# wifi-power.net
KiCad netlist of a schematic drawn in EasyEDA Pro
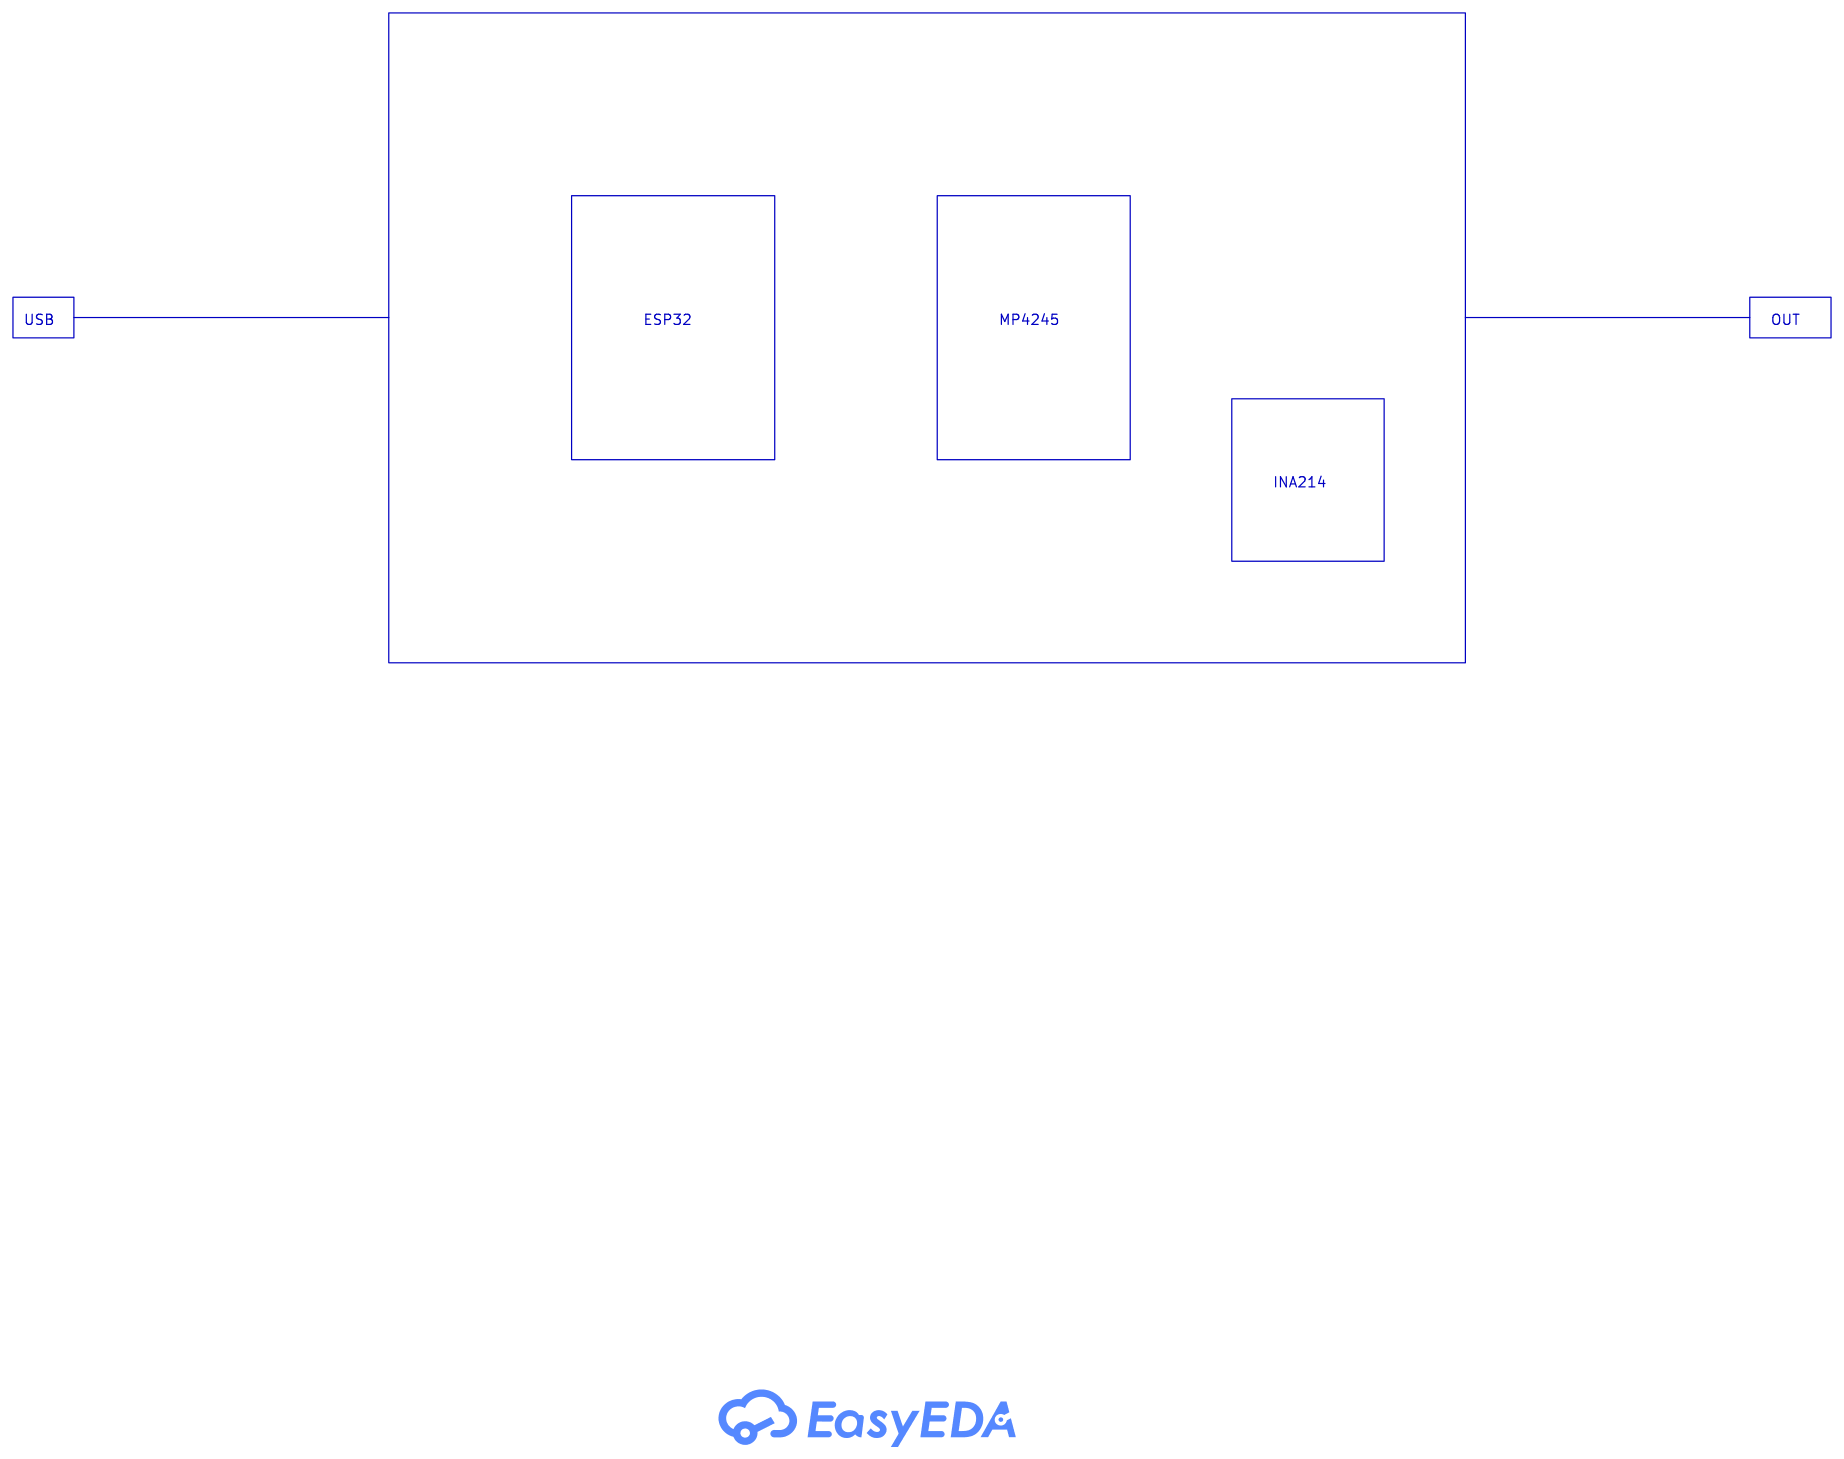
[diagram p0: P1]
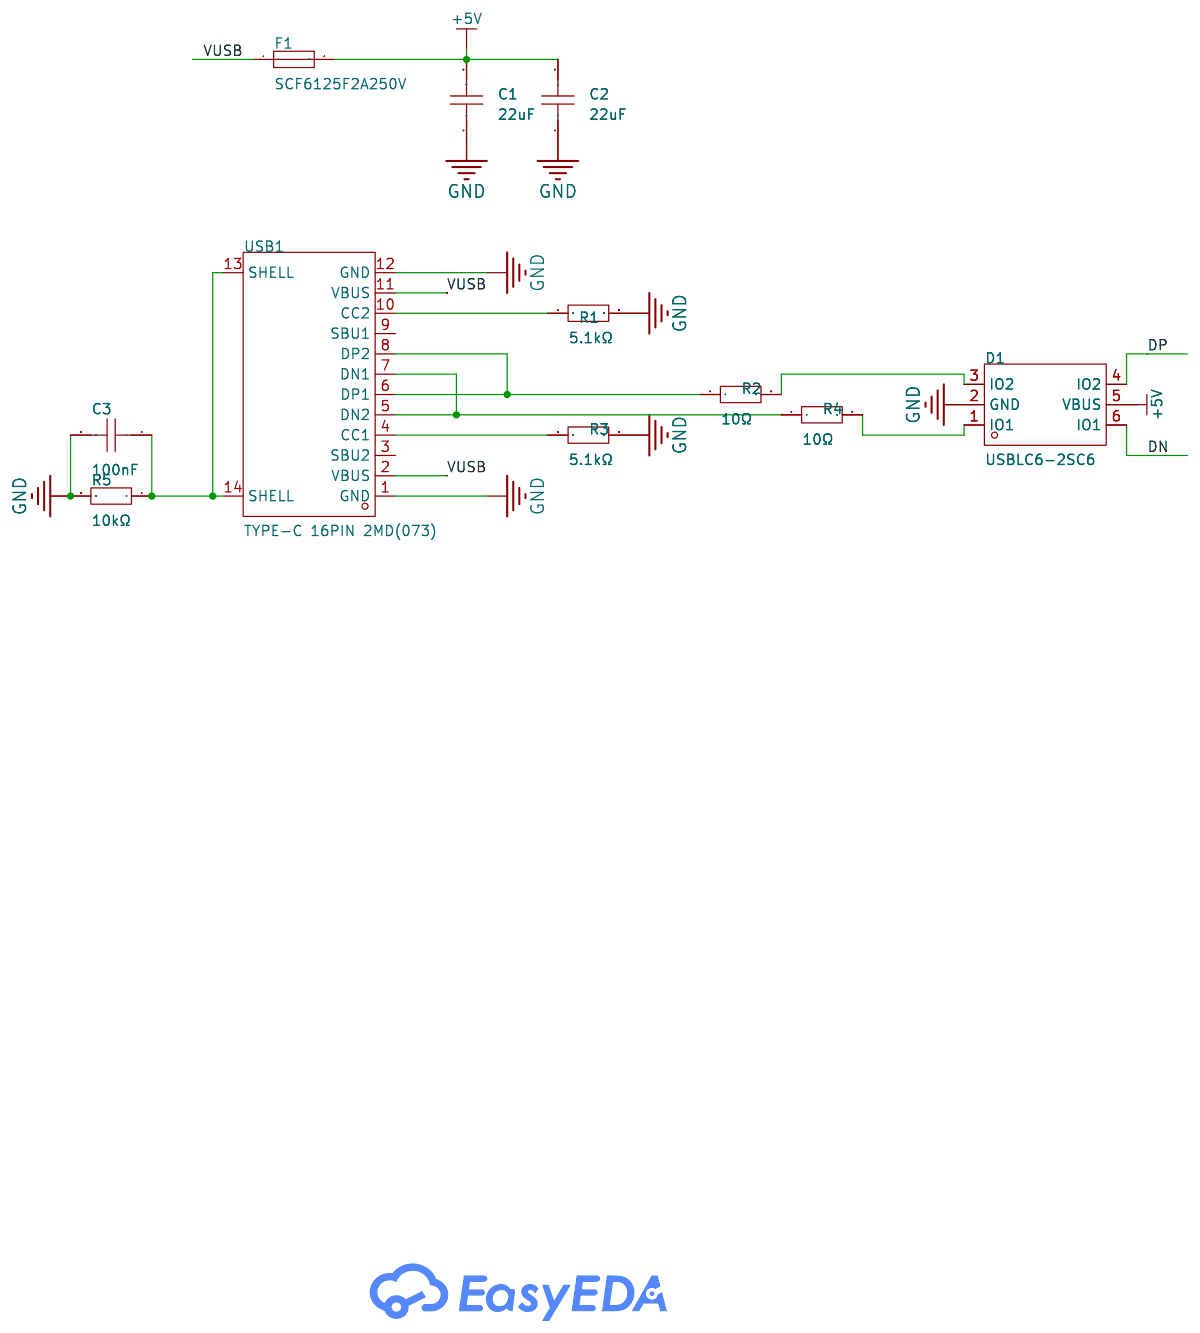
[diagram p1: USB]
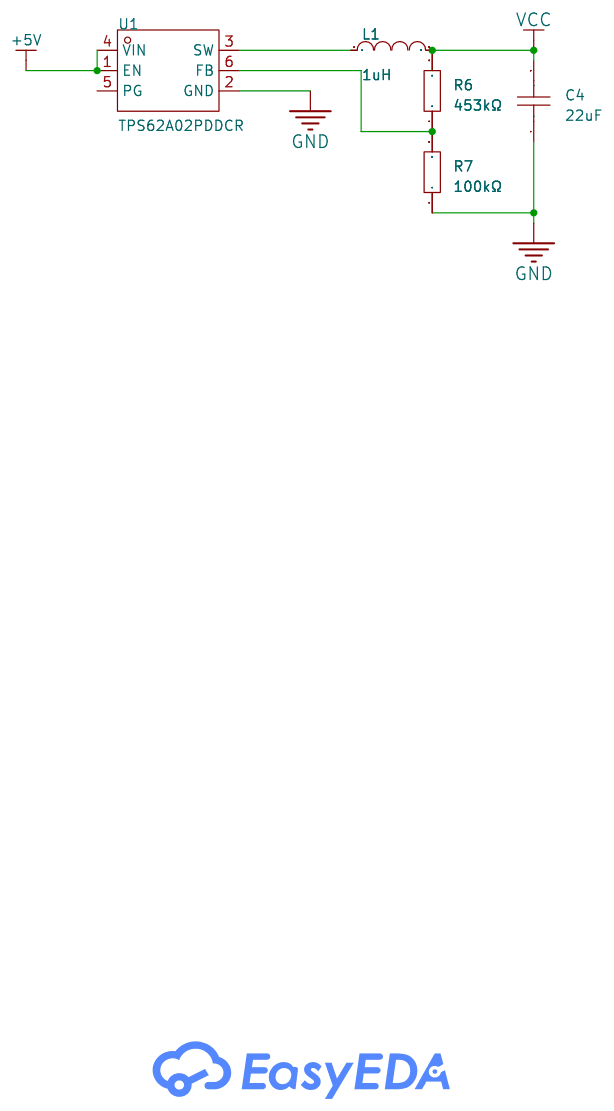
[diagram p2: REG]
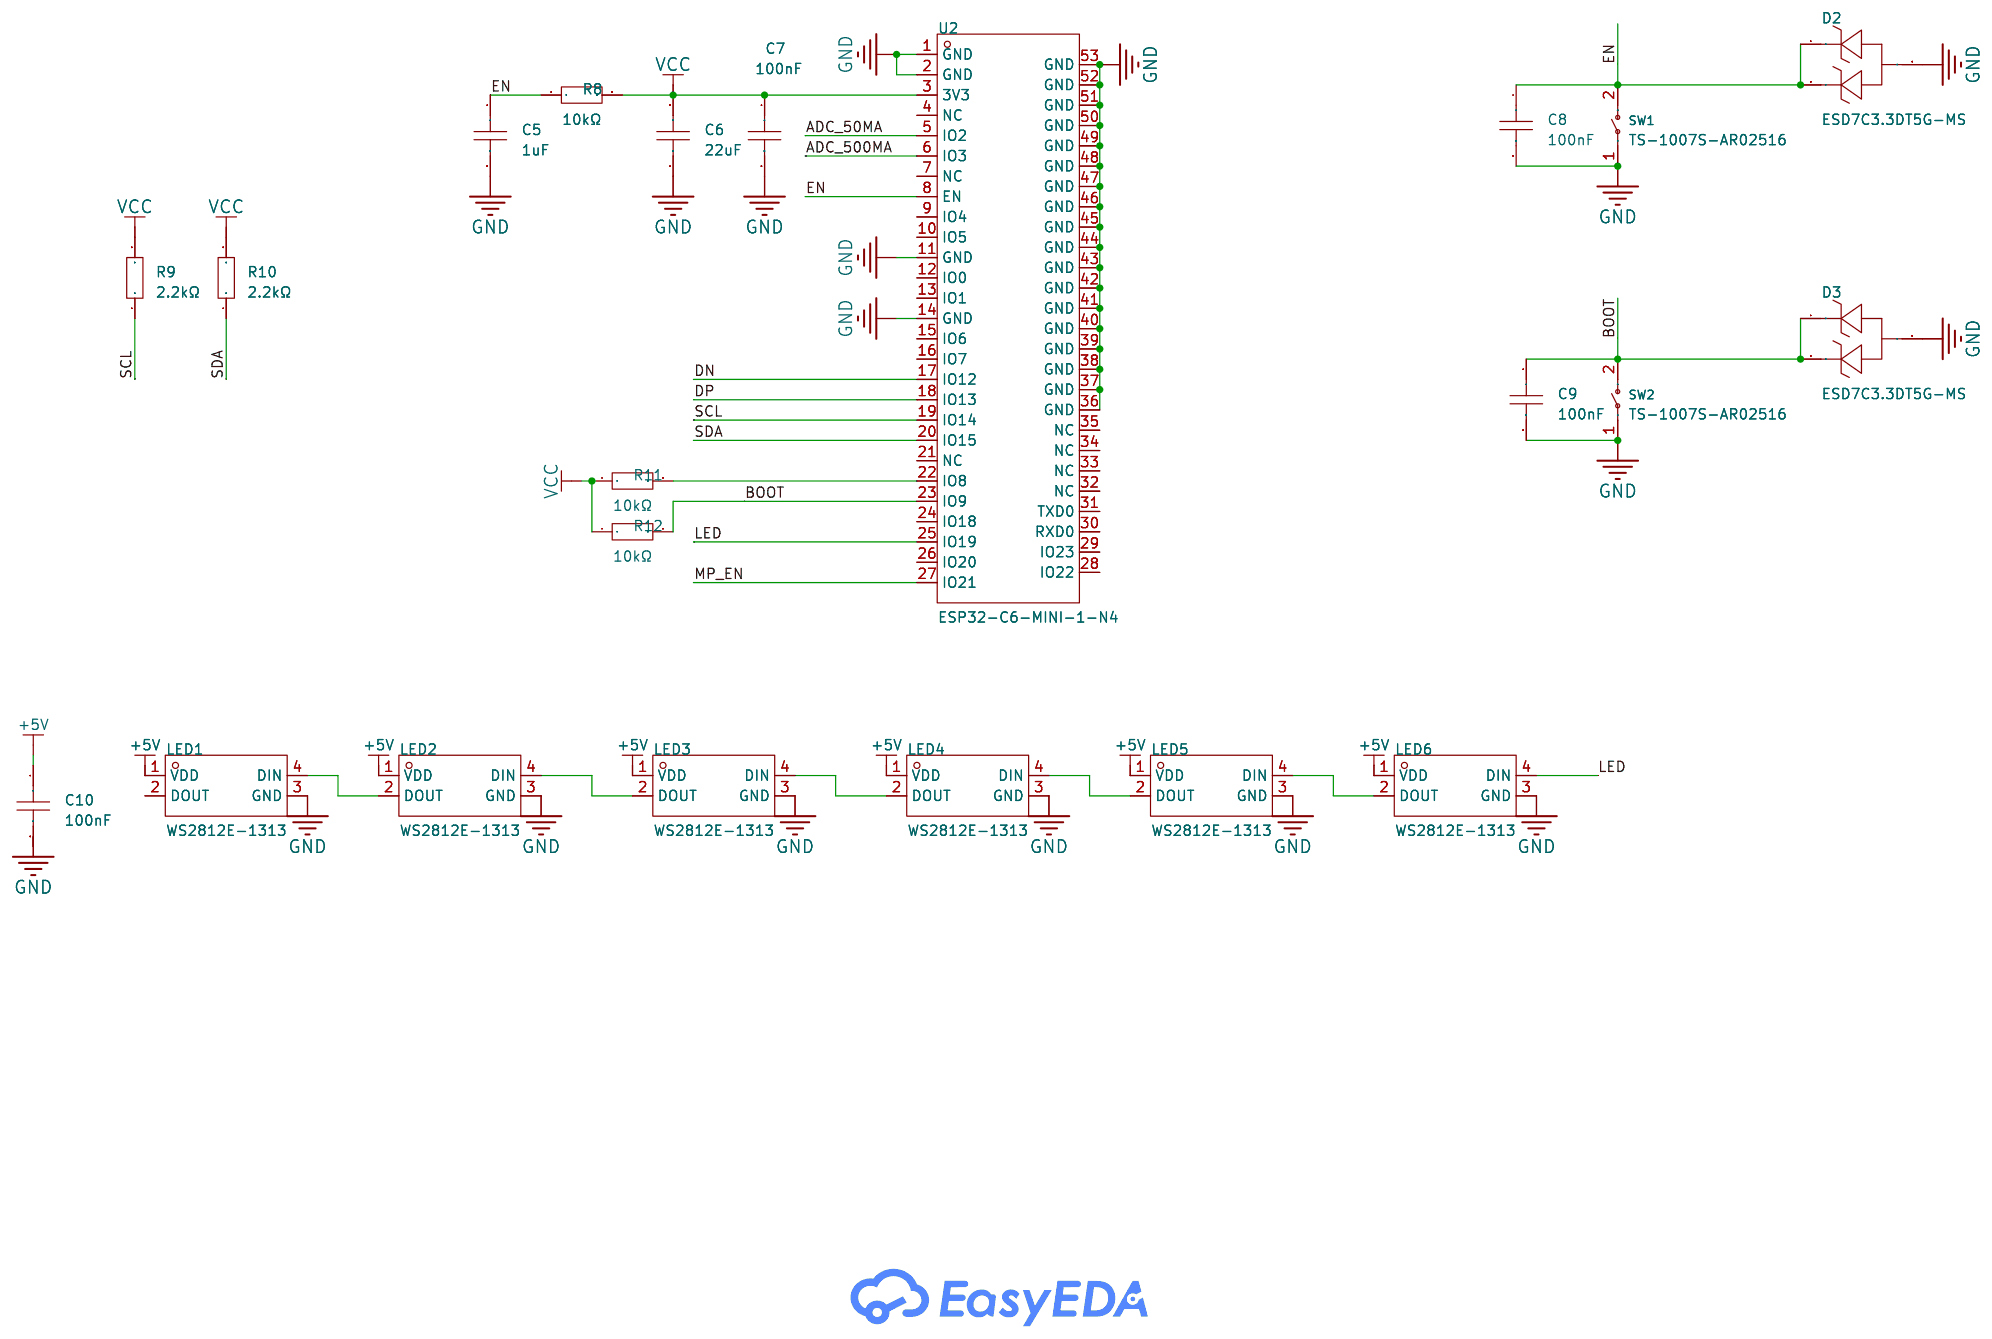
[diagram p3: ESP32]
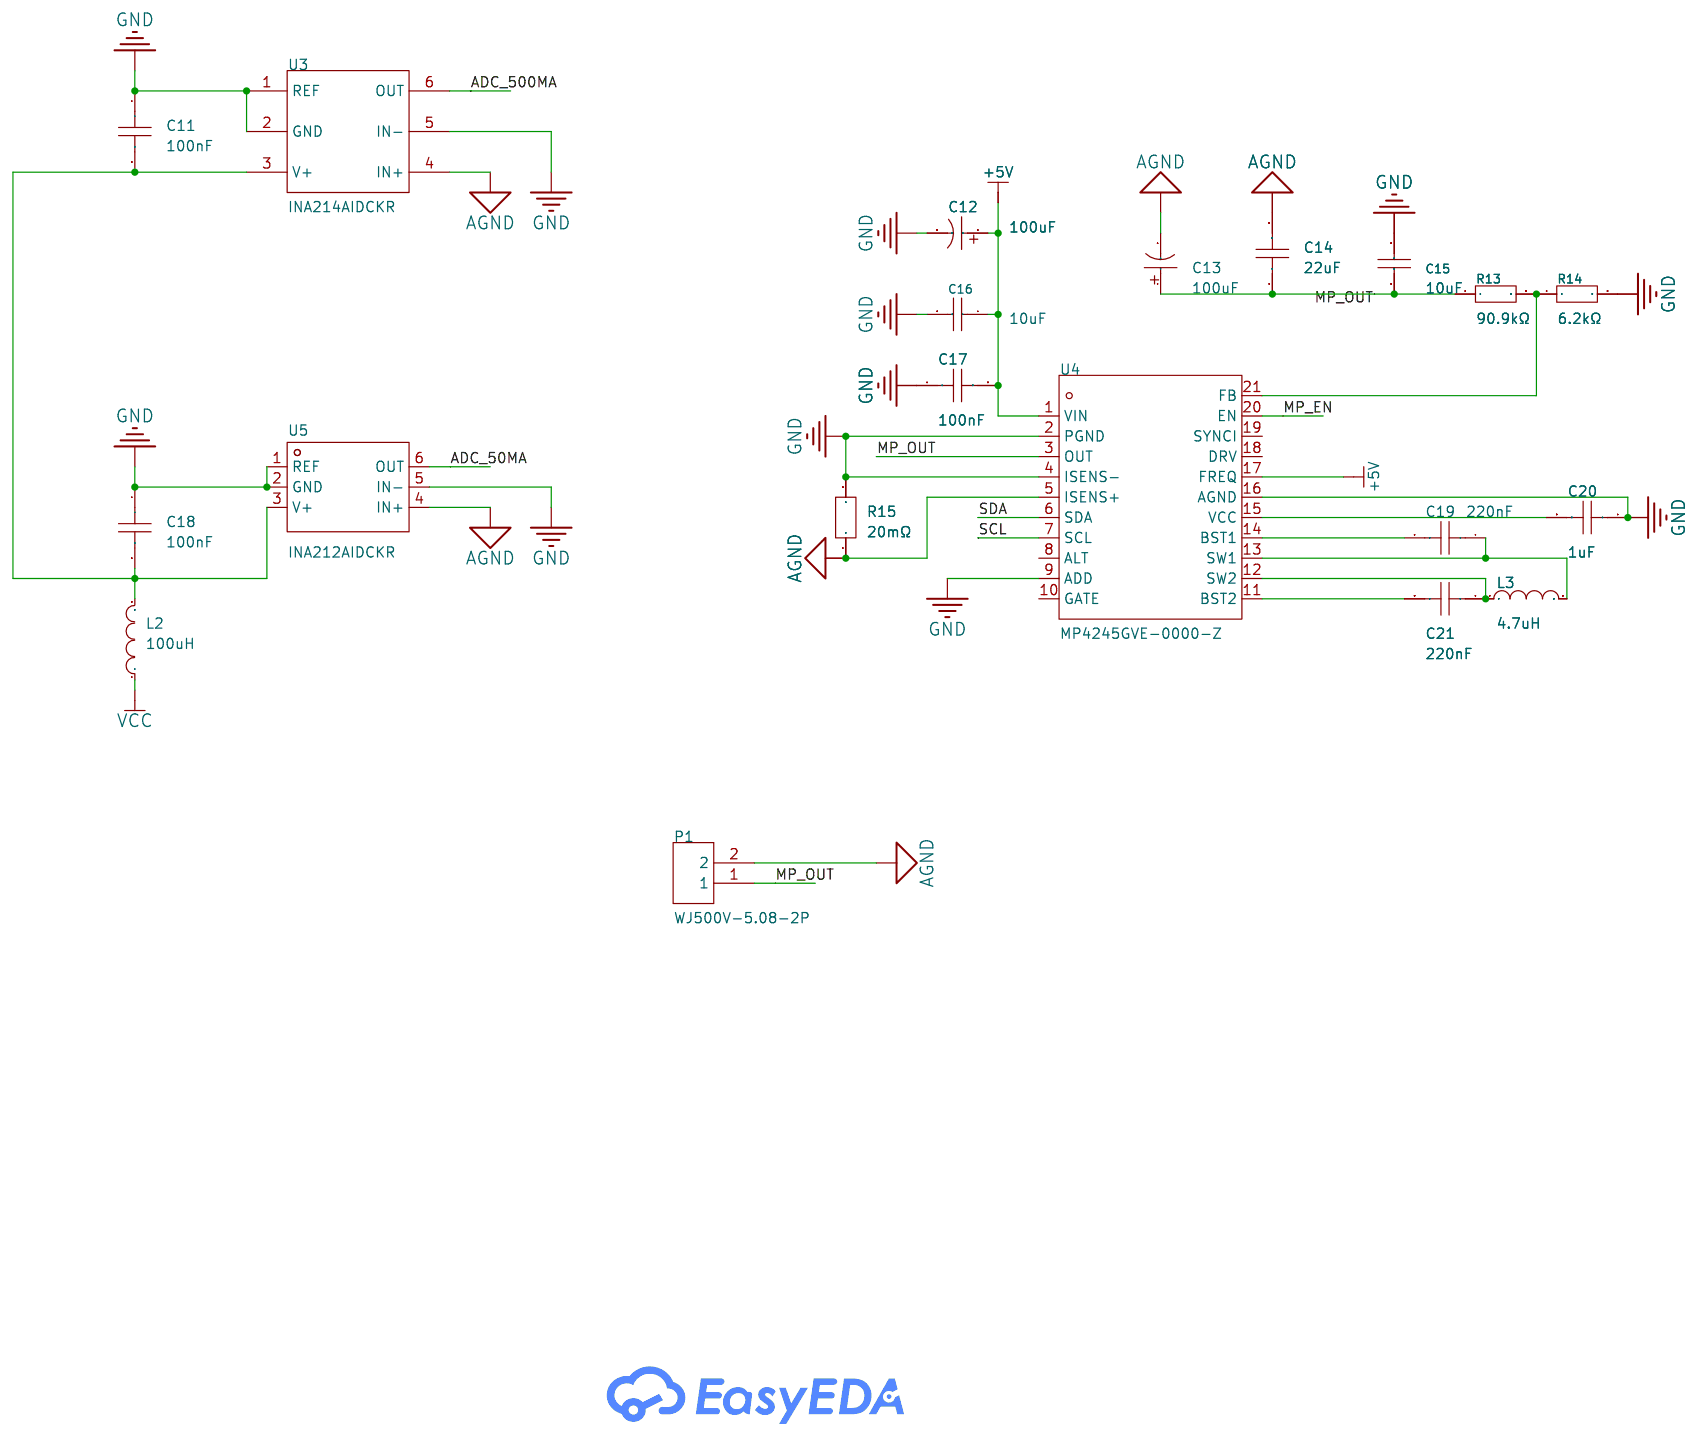
[diagram p4: MP4245]

(export (version "E")
  (design (tool "Eeschema 10.0.6"))
  (components
    (comp (ref "C1")
      (value "22uF")
      (footprint "easyedapro:C0805")
      (fields
        (field (name "Manufacturer Part") "CL21A226MAYNNNE")
        (field (name "Manufacturer") "SAMSUNG(三星)")
      )
      (libsource (lib "easyedapro") (part "CL21A226MAYNNNE"))
    )
    (comp (ref "C2")
      (value "22uF")
      (footprint "easyedapro:C0805")
      (fields
        (field (name "Manufacturer Part") "CL21A226MAYNNNE")
        (field (name "Manufacturer") "SAMSUNG(三星)")
      )
      (libsource (lib "easyedapro") (part "CL21A226MAYNNNE"))
    )
    (comp (ref "C3")
      (value "100nF")
      (footprint "easyedapro:C0603")
      (fields
        (field (name "Manufacturer Part") "CC0603KRX7R9BB104")
        (field (name "Manufacturer") "YAGEO(国巨)")
      )
      (libsource (lib "easyedapro") (part "CAP"))
    )
    (comp (ref "D1")
      (value "USBLC6-2SC6")
      (footprint "easyedapro:SOT-23-6_L2.9-W1.6-P0.95-LS2.8-BL")
      (fields (field (name "Manufacturer") "TECH PUBLIC(台舟)"))
      (libsource (lib "easyedapro") (part "USBLC6-2SC6_C2827654"))
    )
    (comp (ref "F1")
      (value "SCF6125F2A250V")
      (footprint "easyedapro:FUSE-SMD_L6.3-W2.7")
      (fields (field (name "Manufacturer") "SET(赛尔特)"))
      (libsource (lib "easyedapro") (part "SCF6125F2A250V"))
    )
    (comp (ref "R1")
      (value "5.1kΩ")
      (footprint "easyedapro:R0603")
      (fields (field (name "Manufacturer Part") "FRC0603J512 TS") (field (name "Manufacturer") "FOJAN(富捷)"))
      (libsource (lib "easyedapro") (part "Res"))
    )
    (comp (ref "R2")
      (value "10Ω")
      (footprint "easyedapro:R0603")
      (fields
        (field (name "Manufacturer Part") "0603WAF100JT5E")
        (field (name "Manufacturer") "UNI-ROYAL(厚声)")
      )
      (libsource (lib "easyedapro") (part "Res"))
    )
    (comp (ref "R3")
      (value "5.1kΩ")
      (footprint "easyedapro:R0603")
      (fields (field (name "Manufacturer Part") "FRC0603J512 TS") (field (name "Manufacturer") "FOJAN(富捷)"))
      (libsource (lib "easyedapro") (part "Res"))
    )
    (comp (ref "R4")
      (value "10Ω")
      (footprint "easyedapro:R0603")
      (fields
        (field (name "Manufacturer Part") "0603WAF100JT5E")
        (field (name "Manufacturer") "UNI-ROYAL(厚声)")
      )
      (libsource (lib "easyedapro") (part "Res"))
    )
    (comp (ref "R5")
      (value "10kΩ")
      (footprint "easyedapro:R0603")
      (fields (field (name "Manufacturer Part") "FRC0603J103TS") (field (name "Manufacturer") "FOJAN(富捷)"))
      (libsource (lib "easyedapro") (part "Res"))
    )
    (comp (ref "USB1")
      (value "TYPE-C 16PIN 2MD(073)")
      (footprint "easyedapro:USB-C-SMD_TYPE-C-6PIN-2MD-073")
      (fields (field (name "Manufacturer") "SHOU HAN(首韩)"))
      (libsource (lib "easyedapro") (part "TYPE-C 16PIN 2MD(073)"))
    )
    (comp (ref "C4")
      (value "22uF")
      (footprint "easyedapro:C0805")
      (fields
        (field (name "Manufacturer Part") "CL21A226MAYNNNE")
        (field (name "Manufacturer") "SAMSUNG(三星)")
      )
      (libsource (lib "easyedapro") (part "CL21A226MAYNNNE"))
    )
    (comp (ref "L1")
      (value "1uH")
      (footprint "easyedapro:L0806")
      (fields
        (field (name "Manufacturer Part") "DFE201610E-1R0M=P2")
        (field (name "Manufacturer") "muRata(村田)")
      )
      (libsource (lib "easyedapro") (part "DFE201610E-1R0M=P2"))
    )
    (comp (ref "R6")
      (value "453kΩ")
      (footprint "easyedapro:R0603")
      (fields
        (field (name "Manufacturer Part") "0603WAF4533T5E")
        (field (name "Manufacturer") "UNI-ROYAL(厚声)")
      )
      (libsource (lib "easyedapro") (part "Res"))
    )
    (comp (ref "R7")
      (value "100kΩ")
      (footprint "easyedapro:R0603")
      (fields (field (name "Manufacturer Part") "RC0603FR-07100KL") (field (name "Manufacturer") "YAGEO(国巨)"))
      (libsource (lib "easyedapro") (part "Res"))
    )
    (comp (ref "U1")
      (value "TPS62A02PDDCR")
      (footprint "easyedapro:SOT-23-6_L2.9-W1.6-P0.95-LS2.9-BL")
      (fields (field (name "Manufacturer") "TI(德州仪器)"))
      (libsource (lib "easyedapro") (part "TPS62A02PDDCR"))
    )
    (comp (ref "C5")
      (value "1uF")
      (footprint "easyedapro:C0603")
      (fields (field (name "Manufacturer Part") "0603F105Z100CT") (field (name "Manufacturer") "Walsin(华新科)"))
      (libsource (lib "easyedapro") (part "CAP"))
    )
    (comp (ref "C6")
      (value "22uF")
      (footprint "easyedapro:C0805")
      (fields
        (field (name "Manufacturer Part") "CL21A226MAYNNNE")
        (field (name "Manufacturer") "SAMSUNG(三星)")
      )
      (libsource (lib "easyedapro") (part "CL21A226MAYNNNE"))
    )
    (comp (ref "C7")
      (value "100nF")
      (footprint "easyedapro:C0603")
      (fields
        (field (name "Manufacturer Part") "CC0603KRX7R9BB104")
        (field (name "Manufacturer") "YAGEO(国巨)")
      )
      (libsource (lib "easyedapro") (part "CAP"))
    )
    (comp (ref "C8")
      (value "100nF")
      (footprint "easyedapro:C0603")
      (fields
        (field (name "Manufacturer Part") "CC0603KRX7R9BB104")
        (field (name "Manufacturer") "YAGEO(国巨)")
      )
      (libsource (lib "easyedapro") (part "CAP"))
    )
    (comp (ref "C9")
      (value "100nF")
      (footprint "easyedapro:C0603")
      (fields
        (field (name "Manufacturer Part") "CC0603KRX7R9BB104")
        (field (name "Manufacturer") "YAGEO(国巨)")
      )
      (libsource (lib "easyedapro") (part "CAP"))
    )
    (comp (ref "C10")
      (value "100nF")
      (footprint "easyedapro:C0603")
      (fields
        (field (name "Manufacturer Part") "CC0603KRX7R9BB104")
        (field (name "Manufacturer") "YAGEO(国巨)")
      )
      (libsource (lib "easyedapro") (part "CAP"))
    )
    (comp (ref "D2")
      (value "ESD7C3.3DT5G-MS")
      (footprint "easyedapro:SOT-723-3_L1.2-W0.8-P0.80-LS1.2-BR")
      (fields (field (name "Manufacturer") "MSKSEMI(美森科)"))
      (libsource (lib "easyedapro") (part "ESD7C3.3DT5G-MS"))
    )
    (comp (ref "D3")
      (value "ESD7C3.3DT5G-MS")
      (footprint "easyedapro:SOT-723-3_L1.2-W0.8-P0.80-LS1.2-BR")
      (fields (field (name "Manufacturer") "MSKSEMI(美森科)"))
      (libsource (lib "easyedapro") (part "ESD7C3.3DT5G-MS"))
    )
    (comp (ref "LED1")
      (value "WS2812E-1313")
      (footprint "easyedapro:LED-SMD_4P-L1.3-W1.3-P0.80_WS2812E-1313")
      (fields (field (name "Manufacturer") "worldsemi"))
      (libsource (lib "easyedapro") (part "WS2812E-1313"))
    )
    (comp (ref "LED2")
      (value "WS2812E-1313")
      (footprint "easyedapro:LED-SMD_4P-L1.3-W1.3-P0.80_WS2812E-1313")
      (fields (field (name "Manufacturer") "worldsemi"))
      (libsource (lib "easyedapro") (part "WS2812E-1313"))
    )
    (comp (ref "LED3")
      (value "WS2812E-1313")
      (footprint "easyedapro:LED-SMD_4P-L1.3-W1.3-P0.80_WS2812E-1313")
      (fields (field (name "Manufacturer") "worldsemi"))
      (libsource (lib "easyedapro") (part "WS2812E-1313"))
    )
    (comp (ref "LED4")
      (value "WS2812E-1313")
      (footprint "easyedapro:LED-SMD_4P-L1.3-W1.3-P0.80_WS2812E-1313")
      (fields (field (name "Manufacturer") "worldsemi"))
      (libsource (lib "easyedapro") (part "WS2812E-1313"))
    )
    (comp (ref "LED5")
      (value "WS2812E-1313")
      (footprint "easyedapro:LED-SMD_4P-L1.3-W1.3-P0.80_WS2812E-1313")
      (fields (field (name "Manufacturer") "worldsemi"))
      (libsource (lib "easyedapro") (part "WS2812E-1313"))
    )
    (comp (ref "LED6")
      (value "WS2812E-1313")
      (footprint "easyedapro:LED-SMD_4P-L1.3-W1.3-P0.80_WS2812E-1313")
      (fields (field (name "Manufacturer") "worldsemi"))
      (libsource (lib "easyedapro") (part "WS2812E-1313"))
    )
    (comp (ref "R8")
      (value "10kΩ")
      (footprint "easyedapro:R0603")
      (fields (field (name "Manufacturer Part") "FRC0603J103TS") (field (name "Manufacturer") "FOJAN(富捷)"))
      (libsource (lib "easyedapro") (part "Res"))
    )
    (comp (ref "R9")
      (value "2.2kΩ")
      (footprint "easyedapro:R0603")
      (fields (field (name "Manufacturer Part") "FRC0603J222 TS") (field (name "Manufacturer") "FOJAN(富捷)"))
      (libsource (lib "easyedapro") (part "Res"))
    )
    (comp (ref "R10")
      (value "2.2kΩ")
      (footprint "easyedapro:R0603")
      (fields (field (name "Manufacturer Part") "FRC0603J222 TS") (field (name "Manufacturer") "FOJAN(富捷)"))
      (libsource (lib "easyedapro") (part "Res"))
    )
    (comp (ref "R11")
      (value "10kΩ")
      (footprint "easyedapro:R0603")
      (fields (field (name "Manufacturer Part") "FRC0603J103TS") (field (name "Manufacturer") "FOJAN(富捷)"))
      (libsource (lib "easyedapro") (part "Res"))
    )
    (comp (ref "R12")
      (value "10kΩ")
      (footprint "easyedapro:R0603")
      (fields (field (name "Manufacturer Part") "FRC0603J103TS") (field (name "Manufacturer") "FOJAN(富捷)"))
      (libsource (lib "easyedapro") (part "Res"))
    )
    (comp (ref "SW1")
      (value "TS-1007S-AR02516")
      (footprint "easyedapro:SW-SMD_L6.1-W3.6-LS7.9")
      (fields (field (name "Manufacturer") "XUNPU(讯普)"))
      (libsource (lib "easyedapro") (part "TS-1007S-AR02516"))
    )
    (comp (ref "SW2")
      (value "TS-1007S-AR02516")
      (footprint "easyedapro:SW-SMD_L6.1-W3.6-LS7.9")
      (fields (field (name "Manufacturer") "XUNPU(讯普)"))
      (libsource (lib "easyedapro") (part "TS-1007S-AR02516"))
    )
    (comp (ref "U2")
      (value "ESP32-C6-MINI-1-N4")
      (footprint "easyedapro:WIFIM-SMD_61P-L16.6-W13.2-P0.80-ESP32-C6-MINI-1-N4")
      (fields (field (name "Manufacturer") "ESPRESSIF(乐鑫)"))
      (libsource (lib "easyedapro") (part "ESP32-C6-MINI-1-N4"))
    )
    (comp (ref "C11")
      (value "100nF")
      (footprint "easyedapro:C0603")
      (fields
        (field (name "Manufacturer Part") "CC0603KRX7R9BB104")
        (field (name "Manufacturer") "YAGEO(国巨)")
      )
      (libsource (lib "easyedapro") (part "CAP"))
    )
    (comp (ref "C12")
      (value "100uF")
      (footprint "easyedapro:CAP-SMD_BD6.3-L6.6-W6.6-FD")
      (fields
        (field (name "Manufacturer Part") "UWX1C101MCL1GB")
        (field (name "Manufacturer") "Nichicon(尼吉康)")
      )
      (libsource (lib "easyedapro") (part "UWX1C101MCL1GB"))
    )
    (comp (ref "C13")
      (value "100uF")
      (footprint "easyedapro:CAP-SMD_BD6.3-L6.6-W6.6-FD")
      (fields
        (field (name "Manufacturer Part") "UWX1C101MCL1GB")
        (field (name "Manufacturer") "Nichicon(尼吉康)")
      )
      (libsource (lib "easyedapro") (part "UWX1C101MCL1GB"))
    )
    (comp (ref "C14")
      (value "22uF")
      (footprint "easyedapro:C1206")
      (fields
        (field (name "Manufacturer Part") "CL31A226KOHNNNE")
        (field (name "Manufacturer") "SAMSUNG(三星)")
      )
      (libsource (lib "easyedapro") (part "CL31A226KOHNNNE"))
    )
    (comp (ref "C15")
      (value "10uF")
      (footprint "easyedapro:C0805")
      (fields
        (field (name "Manufacturer Part") "CL21A106KOQNNNE")
        (field (name "Manufacturer") "SAMSUNG(三星)")
      )
      (libsource (lib "easyedapro") (part "CL21A106KOQNNNE"))
    )
    (comp (ref "C16")
      (value "10uF")
      (footprint "easyedapro:C0805")
      (fields
        (field (name "Manufacturer Part") "CL21A106KOQNNNE")
        (field (name "Manufacturer") "SAMSUNG(三星)")
      )
      (libsource (lib "easyedapro") (part "CL21A106KOQNNNE"))
    )
    (comp (ref "C17")
      (value "100nF")
      (footprint "easyedapro:C0603")
      (fields
        (field (name "Manufacturer Part") "CC0603KRX7R9BB104")
        (field (name "Manufacturer") "YAGEO(国巨)")
      )
      (libsource (lib "easyedapro") (part "CAP"))
    )
    (comp (ref "C18")
      (value "100nF")
      (footprint "easyedapro:C0603")
      (fields
        (field (name "Manufacturer Part") "CC0603KRX7R9BB104")
        (field (name "Manufacturer") "YAGEO(国巨)")
      )
      (libsource (lib "easyedapro") (part "CAP"))
    )
    (comp (ref "C19")
      (value "220nF")
      (footprint "easyedapro:C0603")
      (libsource (lib "easyedapro") (part "CAP"))
    )
    (comp (ref "C20")
      (value "1uF")
      (footprint "easyedapro:C0603")
      (libsource (lib "easyedapro") (part "CAP"))
    )
    (comp (ref "C21")
      (value "220nF")
      (footprint "easyedapro:C0603")
      (libsource (lib "easyedapro") (part "CAP"))
    )
    (comp (ref "L2")
      (value "100uH")
      (footprint "easyedapro:L0805")
      (fields
        (field (name "Manufacturer Part") "EBLS201212-101K")
        (field (name "Manufacturer") "HYHONGYEX(宏业)")
      )
      (libsource (lib "easyedapro") (part "EBLS201212-101K"))
    )
    (comp (ref "L3")
      (value "4.7uH")
      (footprint "easyedapro:IND-SMD_L5.7-W5.2_CYA0530")
      (fields (field (name "Manufacturer Part") "CYA0530-4.7UH") (field (name "Manufacturer") "SHOU HAN(首韩)"))
      (libsource (lib "easyedapro") (part "CYA0530-4.7UH"))
    )
    (comp (ref "P1")
      (value "WJ500V-5.08-2P")
      (footprint "easyedapro:CONN-TH_2P-P5.00_WJ500V-5.08-2P")
      (fields (field (name "Manufacturer") "KANGNEX(康奈克斯电气)"))
      (libsource (lib "easyedapro") (part "WJ500V-5.08-2P-14-00A"))
    )
    (comp (ref "R13")
      (value "90.9kΩ")
      (footprint "easyedapro:R0603")
      (fields
        (field (name "Manufacturer Part") "RMC060390.9K1%N")
        (field (name "Manufacturer") "Tyohm(幸亚电阻)")
      )
      (libsource (lib "easyedapro") (part "RMC060390.9K1%N"))
    )
    (comp (ref "R14")
      (value "6.2kΩ")
      (footprint "easyedapro:R0603")
      (fields (field (name "Manufacturer Part") "RMC06036.2K1%N") (field (name "Manufacturer") "Tyohm(幸亚电阻)"))
      (libsource (lib "easyedapro") (part "RMC06036.2K1%N"))
    )
    (comp (ref "R15")
      (value "20mΩ")
      (footprint "easyedapro:R0805")
      (fields (field (name "Manufacturer Part") "FCF05FT-R020E") (field (name "Manufacturer") "PSA(信昌电陶)"))
      (libsource (lib "easyedapro") (part "FCF05FT-R020E"))
    )
    (comp (ref "U3")
      (value "INA214AIDCKR")
      (footprint "easyedapro:SC-70-6_L2.2-W1.3-P0.65-LS2.2-BR")
      (fields (field (name "Manufacturer") "TI(德州仪器)"))
      (libsource (lib "easyedapro") (part "INA214AIDCKR"))
    )
    (comp (ref "U4")
      (value "MP4245GVE-0000-Z")
      (footprint "easyedapro:QFN-21_L5.0-W4.0_MP4245GVE")
      (fields (field (name "Manufacturer") "MPS(芯源)"))
      (libsource (lib "easyedapro") (part "MP4245GVE-0000-Z"))
    )
    (comp (ref "U5")
      (value "INA212AIDCKR")
      (footprint "easyedapro:SOT-363_L2.0-W1.3-P0.65-LS2.1-BL")
      (fields (field (name "Manufacturer") "TI(德州仪器)"))
      (libsource (lib "easyedapro") (part "INA212AIDCKR"))
    )
  )
  (nets
    (net (code "1") (name "+5V") (class "Default")
      (node (ref "C1") (pin "2") (pinfunction "2_2") (pintype "unspecified"))
      (node (ref "C10") (pin "1") (pinfunction "1_1") (pintype "input"))
      (node (ref "C12") (pin "1") (pinfunction "1_1") (pintype "input"))
      (node (ref "C16") (pin "1") (pinfunction "1_1") (pintype "input"))
      (node (ref "C17") (pin "2") (pinfunction "2_2") (pintype "input"))
      (node (ref "C2") (pin "2") (pinfunction "2_2") (pintype "unspecified"))
      (node (ref "D1") (pin "5") (pinfunction "VBUS_5") (pintype "unspecified"))
      (node (ref "F1") (pin "2") (pinfunction "2_2") (pintype "unspecified"))
      (node (ref "LED1") (pin "1") (pinfunction "VDD_1") (pintype "unspecified"))
      (node (ref "LED2") (pin "1") (pinfunction "VDD_1") (pintype "unspecified"))
      (node (ref "LED3") (pin "1") (pinfunction "VDD_1") (pintype "unspecified"))
      (node (ref "LED4") (pin "1") (pinfunction "VDD_1") (pintype "unspecified"))
      (node (ref "LED5") (pin "1") (pinfunction "VDD_1") (pintype "unspecified"))
      (node (ref "LED6") (pin "1") (pinfunction "VDD_1") (pintype "unspecified"))
      (node (ref "U1") (pin "1") (pinfunction "EN_1") (pintype "unspecified"))
      (node (ref "U1") (pin "4") (pinfunction "VIN_4") (pintype "unspecified"))
      (node (ref "U4") (pin "1") (pinfunction "VIN_1") (pintype "unspecified"))
      (node (ref "U4") (pin "17") (pinfunction "FREQ_17") (pintype "unspecified"))
    )
    (net (code "2") (name "ADC_50MA") (class "Default")
      (node (ref "U2") (pin "5") (pinfunction "IO2_5") (pintype "unspecified"))
      (node (ref "U5") (pin "6") (pinfunction "OUT_6") (pintype "unspecified"))
    )
    (net (code "3") (name "ADC_500MA") (class "Default")
      (node (ref "U2") (pin "6") (pinfunction "IO3_6") (pintype "unspecified"))
      (node (ref "U3") (pin "6") (pinfunction "OUT_6") (pintype "unspecified"))
    )
    (net (code "4") (name "AGND") (class "Default")
      (node (ref "C13") (pin "2") (pinfunction "2_2") (pintype "input"))
      (node (ref "C14") (pin "2") (pinfunction "2_2") (pintype "unspecified"))
      (node (ref "P1") (pin "2") (pinfunction "2_2") (pintype "unspecified"))
      (node (ref "R15") (pin "1") (pinfunction "1_1") (pintype "unspecified"))
      (node (ref "U3") (pin "4") (pinfunction "IN+_4") (pintype "unspecified"))
      (node (ref "U4") (pin "5") (pinfunction "ISENS+_5") (pintype "unspecified"))
      (node (ref "U5") (pin "4") (pinfunction "IN+_4") (pintype "unspecified"))
    )
    (net (code "5") (name "BOOT") (class "Default")
      (node (ref "C9") (pin "1") (pinfunction "1_1") (pintype "input"))
      (node (ref "D3") (pin "1") (pinfunction "K_1") (pintype "unspecified"))
      (node (ref "D3") (pin "2") (pinfunction "K_2") (pintype "unspecified"))
      (node (ref "R12") (pin "2") (pinfunction "2_2") (pintype "input"))
      (node (ref "SW2") (pin "2") (pinfunction "2_2") (pintype "input"))
      (node (ref "U2") (pin "23") (pinfunction "IO9_23") (pintype "unspecified"))
    )
    (net (code "6") (name "DN") (class "Default")
      (node (ref "D1") (pin "6") (pinfunction "IO1_6") (pintype "unspecified"))
      (node (ref "U2") (pin "17") (pinfunction "IO12_17") (pintype "unspecified"))
    )
    (net (code "7") (name "DP") (class "Default")
      (node (ref "D1") (pin "4") (pinfunction "IO2_4") (pintype "unspecified"))
      (node (ref "U2") (pin "18") (pinfunction "IO13_18") (pintype "unspecified"))
    )
    (net (code "8") (name "EN") (class "Default")
      (node (ref "C5") (pin "1") (pinfunction "1_1") (pintype "input"))
      (node (ref "C8") (pin "1") (pinfunction "1_1") (pintype "input"))
      (node (ref "D2") (pin "1") (pinfunction "K_1") (pintype "unspecified"))
      (node (ref "D2") (pin "2") (pinfunction "K_2") (pintype "unspecified"))
      (node (ref "R8") (pin "1") (pinfunction "1_1") (pintype "input"))
      (node (ref "SW1") (pin "2") (pinfunction "2_2") (pintype "input"))
      (node (ref "U2") (pin "8") (pinfunction "EN_8") (pintype "unspecified"))
    )
    (net (code "9") (name "GND") (class "Default")
      (node (ref "C1") (pin "1") (pinfunction "1_1") (pintype "unspecified"))
      (node (ref "C10") (pin "2") (pinfunction "2_2") (pintype "input"))
      (node (ref "C11") (pin "1") (pinfunction "1_1") (pintype "input"))
      (node (ref "C12") (pin "2") (pinfunction "2_2") (pintype "input"))
      (node (ref "C15") (pin "2") (pinfunction "2_2") (pintype "input"))
      (node (ref "C16") (pin "2") (pinfunction "2_2") (pintype "input"))
      (node (ref "C17") (pin "1") (pinfunction "1_1") (pintype "input"))
      (node (ref "C18") (pin "1") (pinfunction "1_1") (pintype "input"))
      (node (ref "C2") (pin "1") (pinfunction "1_1") (pintype "unspecified"))
      (node (ref "C20") (pin "1") (pinfunction "1_1") (pintype "input"))
      (node (ref "C3") (pin "2") (pinfunction "2_2") (pintype "input"))
      (node (ref "C4") (pin "1") (pinfunction "1_1") (pintype "unspecified"))
      (node (ref "C5") (pin "2") (pinfunction "2_2") (pintype "input"))
      (node (ref "C6") (pin "1") (pinfunction "1_1") (pintype "unspecified"))
      (node (ref "C7") (pin "2") (pinfunction "2_2") (pintype "input"))
      (node (ref "C8") (pin "2") (pinfunction "2_2") (pintype "input"))
      (node (ref "C9") (pin "2") (pinfunction "2_2") (pintype "input"))
      (node (ref "D1") (pin "2") (pinfunction "GND_2") (pintype "unspecified"))
      (node (ref "D2") (pin "3") (pinfunction "A_3") (pintype "unspecified"))
      (node (ref "D3") (pin "3") (pinfunction "A_3") (pintype "unspecified"))
      (node (ref "LED1") (pin "3") (pinfunction "GND_3") (pintype "unspecified"))
      (node (ref "LED2") (pin "3") (pinfunction "GND_3") (pintype "unspecified"))
      (node (ref "LED3") (pin "3") (pinfunction "GND_3") (pintype "unspecified"))
      (node (ref "LED4") (pin "3") (pinfunction "GND_3") (pintype "unspecified"))
      (node (ref "LED5") (pin "3") (pinfunction "GND_3") (pintype "unspecified"))
      (node (ref "LED6") (pin "3") (pinfunction "GND_3") (pintype "unspecified"))
      (node (ref "R1") (pin "2") (pinfunction "2_2") (pintype "input"))
      (node (ref "R14") (pin "2") (pinfunction "2_2") (pintype "input"))
      (node (ref "R15") (pin "2") (pinfunction "2_2") (pintype "unspecified"))
      (node (ref "R3") (pin "2") (pinfunction "2_2") (pintype "input"))
      (node (ref "R5") (pin "2") (pinfunction "2_2") (pintype "input"))
      (node (ref "R7") (pin "1") (pinfunction "1_1") (pintype "input"))
      (node (ref "SW1") (pin "1") (pinfunction "1_1") (pintype "input"))
      (node (ref "SW2") (pin "1") (pinfunction "1_1") (pintype "input"))
      (node (ref "U1") (pin "2") (pinfunction "GND_2") (pintype "unspecified"))
      (node (ref "U2") (pin "1") (pinfunction "GND_1") (pintype "unspecified"))
      (node (ref "U2") (pin "11") (pinfunction "GND_11") (pintype "unspecified"))
      (node (ref "U2") (pin "14") (pinfunction "GND_14") (pintype "unspecified"))
      (node (ref "U2") (pin "2") (pinfunction "GND_2") (pintype "unspecified"))
      (node (ref "U2") (pin "36") (pinfunction "GND_36") (pintype "unspecified"))
      (node (ref "U2") (pin "37") (pinfunction "GND_37") (pintype "unspecified"))
      (node (ref "U2") (pin "38") (pinfunction "GND_38") (pintype "unspecified"))
      (node (ref "U2") (pin "39") (pinfunction "GND_39") (pintype "unspecified"))
      (node (ref "U2") (pin "40") (pinfunction "GND_40") (pintype "unspecified"))
      (node (ref "U2") (pin "41") (pinfunction "GND_41") (pintype "unspecified"))
      (node (ref "U2") (pin "42") (pinfunction "GND_42") (pintype "unspecified"))
      (node (ref "U2") (pin "43") (pinfunction "GND_43") (pintype "unspecified"))
      (node (ref "U2") (pin "44") (pinfunction "GND_44") (pintype "unspecified"))
      (node (ref "U2") (pin "45") (pinfunction "GND_45") (pintype "unspecified"))
      (node (ref "U2") (pin "46") (pinfunction "GND_46") (pintype "unspecified"))
      (node (ref "U2") (pin "47") (pinfunction "GND_47") (pintype "unspecified"))
      (node (ref "U2") (pin "48") (pinfunction "GND_48") (pintype "unspecified"))
      (node (ref "U2") (pin "49") (pinfunction "GND_49") (pintype "unspecified"))
      (node (ref "U2") (pin "50") (pinfunction "GND_50") (pintype "unspecified"))
      (node (ref "U2") (pin "51") (pinfunction "GND_51") (pintype "unspecified"))
      (node (ref "U2") (pin "52") (pinfunction "GND_52") (pintype "unspecified"))
      (node (ref "U2") (pin "53") (pinfunction "GND_53") (pintype "unspecified"))
      (node (ref "U3") (pin "1") (pinfunction "REF_1") (pintype "unspecified"))
      (node (ref "U3") (pin "2") (pinfunction "GND_2") (pintype "unspecified"))
      (node (ref "U3") (pin "5") (pinfunction "IN-_5") (pintype "unspecified"))
      (node (ref "U4") (pin "16") (pinfunction "AGND_16") (pintype "unspecified"))
      (node (ref "U4") (pin "2") (pinfunction "PGND_2") (pintype "unspecified"))
      (node (ref "U4") (pin "4") (pinfunction "ISENS-_4") (pintype "unspecified"))
      (node (ref "U4") (pin "9") (pinfunction "ADD_9") (pintype "unspecified"))
      (node (ref "U5") (pin "1") (pinfunction "REF_1") (pintype "unspecified"))
      (node (ref "U5") (pin "2") (pinfunction "GND_2") (pintype "unspecified"))
      (node (ref "U5") (pin "5") (pinfunction "IN-_5") (pintype "unspecified"))
      (node (ref "USB1") (pin "1") (pinfunction "GND_1") (pintype "unspecified"))
      (node (ref "USB1") (pin "12") (pinfunction "GND_12") (pintype "unspecified"))
    )
    (net (code "10") (name "LED") (class "Default")
      (node (ref "LED6") (pin "4") (pinfunction "DIN_4") (pintype "unspecified"))
      (node (ref "U2") (pin "25") (pinfunction "IO19_25") (pintype "unspecified"))
    )
    (net (code "11") (name "MP_EN") (class "Default")
      (node (ref "U2") (pin "27") (pinfunction "IO21_27") (pintype "unspecified"))
      (node (ref "U4") (pin "20") (pinfunction "EN_20") (pintype "unspecified"))
    )
    (net (code "12") (name "MP_OUT") (class "Default")
      (node (ref "C13") (pin "1") (pinfunction "1_1") (pintype "input"))
      (node (ref "C14") (pin "1") (pinfunction "1_1") (pintype "unspecified"))
      (node (ref "C15") (pin "1") (pinfunction "1_1") (pintype "input"))
      (node (ref "P1") (pin "1") (pinfunction "1_1") (pintype "unspecified"))
      (node (ref "R13") (pin "1") (pinfunction "1_1") (pintype "input"))
      (node (ref "U4") (pin "3") (pinfunction "OUT_3") (pintype "unspecified"))
    )
    (net (code "13") (name "Net-(C3-Pad1)") (class "Default")
      (node (ref "C3") (pin "1") (pinfunction "1_1") (pintype "input"))
      (node (ref "R5") (pin "1") (pinfunction "1_1") (pintype "input"))
      (node (ref "USB1") (pin "13") (pinfunction "SHELL_13") (pintype "unspecified"))
      (node (ref "USB1") (pin "14") (pinfunction "SHELL_14") (pintype "unspecified"))
    )
    (net (code "14") (name "Net-(D1-IO1-Pad1)") (class "Default")
      (node (ref "D1") (pin "1") (pinfunction "IO1_1") (pintype "unspecified"))
      (node (ref "R4") (pin "2") (pinfunction "2_2") (pintype "input"))
    )
    (net (code "15") (name "Net-(D1-IO2-Pad3)") (class "Default")
      (node (ref "D1") (pin "3") (pinfunction "IO2_3") (pintype "unspecified"))
      (node (ref "R2") (pin "2") (pinfunction "2_2") (pintype "input"))
    )
    (net (code "16") (name "Net-(LED1-DIN)") (class "Default")
      (node (ref "LED1") (pin "4") (pinfunction "DIN_4") (pintype "unspecified"))
      (node (ref "LED2") (pin "2") (pinfunction "DOUT_2") (pintype "unspecified"))
    )
    (net (code "17") (name "Net-(LED2-DIN)") (class "Default")
      (node (ref "LED2") (pin "4") (pinfunction "DIN_4") (pintype "unspecified"))
      (node (ref "LED3") (pin "2") (pinfunction "DOUT_2") (pintype "unspecified"))
    )
    (net (code "18") (name "Net-(LED3-DIN)") (class "Default")
      (node (ref "LED3") (pin "4") (pinfunction "DIN_4") (pintype "unspecified"))
      (node (ref "LED4") (pin "2") (pinfunction "DOUT_2") (pintype "unspecified"))
    )
    (net (code "19") (name "Net-(LED4-DIN)") (class "Default")
      (node (ref "LED4") (pin "4") (pinfunction "DIN_4") (pintype "unspecified"))
      (node (ref "LED5") (pin "2") (pinfunction "DOUT_2") (pintype "unspecified"))
    )
    (net (code "20") (name "Net-(LED5-DIN)") (class "Default")
      (node (ref "LED5") (pin "4") (pinfunction "DIN_4") (pintype "unspecified"))
      (node (ref "LED6") (pin "2") (pinfunction "DOUT_2") (pintype "unspecified"))
    )
    (net (code "21") (name "Net-(U1-FB)") (class "Default")
      (node (ref "R6") (pin "1") (pinfunction "1_1") (pintype "input"))
      (node (ref "R7") (pin "2") (pinfunction "2_2") (pintype "input"))
      (node (ref "U1") (pin "6") (pinfunction "FB_6") (pintype "unspecified"))
    )
    (net (code "22") (name "Net-(U1-SW)") (class "Default")
      (node (ref "L1") (pin "1") (pinfunction "1_1") (pintype "unspecified"))
      (node (ref "U1") (pin "3") (pinfunction "SW_3") (pintype "unspecified"))
    )
    (net (code "23") (name "Net-(U2-IO8)") (class "Default")
      (node (ref "R11") (pin "2") (pinfunction "2_2") (pintype "input"))
      (node (ref "U2") (pin "22") (pinfunction "IO8_22") (pintype "unspecified"))
    )
    (net (code "24") (name "Net-(U3-V+)") (class "Default")
      (node (ref "C11") (pin "2") (pinfunction "2_2") (pintype "input"))
      (node (ref "C18") (pin "2") (pinfunction "2_2") (pintype "input"))
      (node (ref "L2") (pin "2") (pinfunction "2_2") (pintype "unspecified"))
      (node (ref "U3") (pin "3") (pinfunction "V+_3") (pintype "unspecified"))
      (node (ref "U5") (pin "3") (pinfunction "V+_3") (pintype "unspecified"))
    )
    (net (code "25") (name "Net-(U4-BST1)") (class "Default")
      (node (ref "C19") (pin "2") (pinfunction "2_2") (pintype "input"))
      (node (ref "U4") (pin "14") (pinfunction "BST1_14") (pintype "unspecified"))
    )
    (net (code "26") (name "Net-(U4-BST2)") (class "Default")
      (node (ref "C21") (pin "2") (pinfunction "2_2") (pintype "input"))
      (node (ref "U4") (pin "11") (pinfunction "BST2_11") (pintype "unspecified"))
    )
    (net (code "27") (name "Net-(U4-FB)") (class "Default")
      (node (ref "R13") (pin "2") (pinfunction "2_2") (pintype "input"))
      (node (ref "R14") (pin "1") (pinfunction "1_1") (pintype "input"))
      (node (ref "U4") (pin "21") (pinfunction "FB_21") (pintype "unspecified"))
    )
    (net (code "28") (name "Net-(U4-SW1)") (class "Default")
      (node (ref "C19") (pin "1") (pinfunction "1_1") (pintype "input"))
      (node (ref "L3") (pin "2") (pinfunction "2_2") (pintype "unspecified"))
      (node (ref "U4") (pin "13") (pinfunction "SW1_13") (pintype "unspecified"))
    )
    (net (code "29") (name "Net-(U4-SW2)") (class "Default")
      (node (ref "C21") (pin "1") (pinfunction "1_1") (pintype "input"))
      (node (ref "L3") (pin "1") (pinfunction "1_1") (pintype "unspecified"))
      (node (ref "U4") (pin "12") (pinfunction "SW2_12") (pintype "unspecified"))
    )
    (net (code "30") (name "Net-(U4-VCC)") (class "Default")
      (node (ref "C20") (pin "2") (pinfunction "2_2") (pintype "input"))
      (node (ref "U4") (pin "15") (pinfunction "VCC_15") (pintype "unspecified"))
    )
    (net (code "31") (name "Net-(USB1-CC1)") (class "Default")
      (node (ref "R3") (pin "1") (pinfunction "1_1") (pintype "input"))
      (node (ref "USB1") (pin "4") (pinfunction "CC1_4") (pintype "unspecified"))
    )
    (net (code "32") (name "Net-(USB1-CC2)") (class "Default")
      (node (ref "R1") (pin "1") (pinfunction "1_1") (pintype "input"))
      (node (ref "USB1") (pin "10") (pinfunction "CC2_10") (pintype "unspecified"))
    )
    (net (code "33") (name "Net-(USB1-DN1)") (class "Default")
      (node (ref "R4") (pin "1") (pinfunction "1_1") (pintype "input"))
      (node (ref "USB1") (pin "5") (pinfunction "DN2_5") (pintype "unspecified"))
      (node (ref "USB1") (pin "7") (pinfunction "DN1_7") (pintype "unspecified"))
    )
    (net (code "34") (name "Net-(USB1-DP1)") (class "Default")
      (node (ref "R2") (pin "1") (pinfunction "1_1") (pintype "input"))
      (node (ref "USB1") (pin "6") (pinfunction "DP1_6") (pintype "unspecified"))
      (node (ref "USB1") (pin "8") (pinfunction "DP2_8") (pintype "unspecified"))
    )
    (net (code "35") (name "SCL") (class "Default")
      (node (ref "R9") (pin "1") (pinfunction "1_1") (pintype "input"))
      (node (ref "U2") (pin "19") (pinfunction "IO14_19") (pintype "unspecified"))
      (node (ref "U4") (pin "7") (pinfunction "SCL_7") (pintype "unspecified"))
    )
    (net (code "36") (name "SDA") (class "Default")
      (node (ref "R10") (pin "1") (pinfunction "1_1") (pintype "input"))
      (node (ref "U2") (pin "20") (pinfunction "IO15_20") (pintype "unspecified"))
      (node (ref "U4") (pin "6") (pinfunction "SDA_6") (pintype "unspecified"))
    )
    (net (code "37") (name "VCC") (class "Default")
      (node (ref "C4") (pin "2") (pinfunction "2_2") (pintype "unspecified"))
      (node (ref "C6") (pin "2") (pinfunction "2_2") (pintype "unspecified"))
      (node (ref "C7") (pin "1") (pinfunction "1_1") (pintype "input"))
      (node (ref "L1") (pin "2") (pinfunction "2_2") (pintype "unspecified"))
      (node (ref "L2") (pin "1") (pinfunction "1_1") (pintype "unspecified"))
      (node (ref "R10") (pin "2") (pinfunction "2_2") (pintype "input"))
      (node (ref "R11") (pin "1") (pinfunction "1_1") (pintype "input"))
      (node (ref "R12") (pin "1") (pinfunction "1_1") (pintype "input"))
      (node (ref "R6") (pin "2") (pinfunction "2_2") (pintype "input"))
      (node (ref "R8") (pin "2") (pinfunction "2_2") (pintype "input"))
      (node (ref "R9") (pin "2") (pinfunction "2_2") (pintype "input"))
      (node (ref "U2") (pin "3") (pinfunction "3V3_3") (pintype "unspecified"))
    )
    (net (code "38") (name "VUSB") (class "Default")
      (node (ref "F1") (pin "1") (pinfunction "1_1") (pintype "unspecified"))
      (node (ref "USB1") (pin "11") (pinfunction "VBUS_11") (pintype "unspecified"))
      (node (ref "USB1") (pin "2") (pinfunction "VBUS_2") (pintype "unspecified"))
    )
    (net (code "39") (name "unconnected-(LED1-DOUT-Pad2)") (class "Default")
      (node (ref "LED1") (pin "2") (pinfunction "DOUT_2") (pintype "unspecified"))
    )
    (net (code "40") (name "unconnected-(U1-PG-Pad5)") (class "Default")
      (node (ref "U1") (pin "5") (pinfunction "PG_5") (pintype "unspecified"))
    )
    (net (code "41") (name "unconnected-(U2-IO0-Pad12)") (class "Default")
      (node (ref "U2") (pin "12") (pinfunction "IO0_12") (pintype "unspecified"))
    )
    (net (code "42") (name "unconnected-(U2-IO1-Pad13)") (class "Default")
      (node (ref "U2") (pin "13") (pinfunction "IO1_13") (pintype "unspecified"))
    )
    (net (code "43") (name "unconnected-(U2-IO4-Pad9)") (class "Default")
      (node (ref "U2") (pin "9") (pinfunction "IO4_9") (pintype "unspecified"))
    )
    (net (code "44") (name "unconnected-(U2-IO5-Pad10)") (class "Default")
      (node (ref "U2") (pin "10") (pinfunction "IO5_10") (pintype "unspecified"))
    )
    (net (code "45") (name "unconnected-(U2-IO6-Pad15)") (class "Default")
      (node (ref "U2") (pin "15") (pinfunction "IO6_15") (pintype "unspecified"))
    )
    (net (code "46") (name "unconnected-(U2-IO7-Pad16)") (class "Default")
      (node (ref "U2") (pin "16") (pinfunction "IO7_16") (pintype "unspecified"))
    )
    (net (code "47") (name "unconnected-(U2-IO18-Pad24)") (class "Default")
      (node (ref "U2") (pin "24") (pinfunction "IO18_24") (pintype "unspecified"))
    )
    (net (code "48") (name "unconnected-(U2-IO20-Pad26)") (class "Default")
      (node (ref "U2") (pin "26") (pinfunction "IO20_26") (pintype "unspecified"))
    )
    (net (code "49") (name "unconnected-(U2-IO22-Pad28)") (class "Default")
      (node (ref "U2") (pin "28") (pinfunction "IO22_28") (pintype "unspecified"))
    )
    (net (code "50") (name "unconnected-(U2-IO23-Pad29)") (class "Default")
      (node (ref "U2") (pin "29") (pinfunction "IO23_29") (pintype "unspecified"))
    )
    (net (code "51") (name "unconnected-(U2-NC-Pad4)") (class "Default")
      (node (ref "U2") (pin "4") (pinfunction "NC_4") (pintype "unspecified"))
    )
    (net (code "52") (name "unconnected-(U2-NC-Pad7)") (class "Default")
      (node (ref "U2") (pin "7") (pinfunction "NC_7") (pintype "unspecified"))
    )
    (net (code "53") (name "unconnected-(U2-NC-Pad21)") (class "Default")
      (node (ref "U2") (pin "21") (pinfunction "NC_21") (pintype "unspecified"))
    )
    (net (code "54") (name "unconnected-(U2-NC-Pad32)") (class "Default")
      (node (ref "U2") (pin "32") (pinfunction "NC_32") (pintype "unspecified"))
    )
    (net (code "55") (name "unconnected-(U2-NC-Pad33)") (class "Default")
      (node (ref "U2") (pin "33") (pinfunction "NC_33") (pintype "unspecified"))
    )
    (net (code "56") (name "unconnected-(U2-NC-Pad34)") (class "Default")
      (node (ref "U2") (pin "34") (pinfunction "NC_34") (pintype "unspecified"))
    )
    (net (code "57") (name "unconnected-(U2-NC-Pad35)") (class "Default")
      (node (ref "U2") (pin "35") (pinfunction "NC_35") (pintype "unspecified"))
    )
    (net (code "58") (name "unconnected-(U2-RXD0-Pad30)") (class "Default")
      (node (ref "U2") (pin "30") (pinfunction "RXD0_30") (pintype "unspecified"))
    )
    (net (code "59") (name "unconnected-(U2-TXD0-Pad31)") (class "Default")
      (node (ref "U2") (pin "31") (pinfunction "TXD0_31") (pintype "unspecified"))
    )
    (net (code "60") (name "unconnected-(U4-ALT-Pad8)") (class "Default")
      (node (ref "U4") (pin "8") (pinfunction "ALT_8") (pintype "unspecified"))
    )
    (net (code "61") (name "unconnected-(U4-DRV-Pad18)") (class "Default")
      (node (ref "U4") (pin "18") (pinfunction "DRV_18") (pintype "unspecified"))
    )
    (net (code "62") (name "unconnected-(U4-GATE-Pad10)") (class "Default")
      (node (ref "U4") (pin "10") (pinfunction "GATE_10") (pintype "unspecified"))
    )
    (net (code "63") (name "unconnected-(U4-SYNCI-Pad19)") (class "Default")
      (node (ref "U4") (pin "19") (pinfunction "SYNCI_19") (pintype "unspecified"))
    )
    (net (code "64") (name "unconnected-(USB1-SBU1-Pad9)") (class "Default")
      (node (ref "USB1") (pin "9") (pinfunction "SBU1_9") (pintype "unspecified"))
    )
    (net (code "65") (name "unconnected-(USB1-SBU2-Pad3)") (class "Default")
      (node (ref "USB1") (pin "3") (pinfunction "SBU2_3") (pintype "unspecified"))
    )
  )
)
